# cannonrobot.net
KiCad netlist of a schematic drawn in Altium Designer
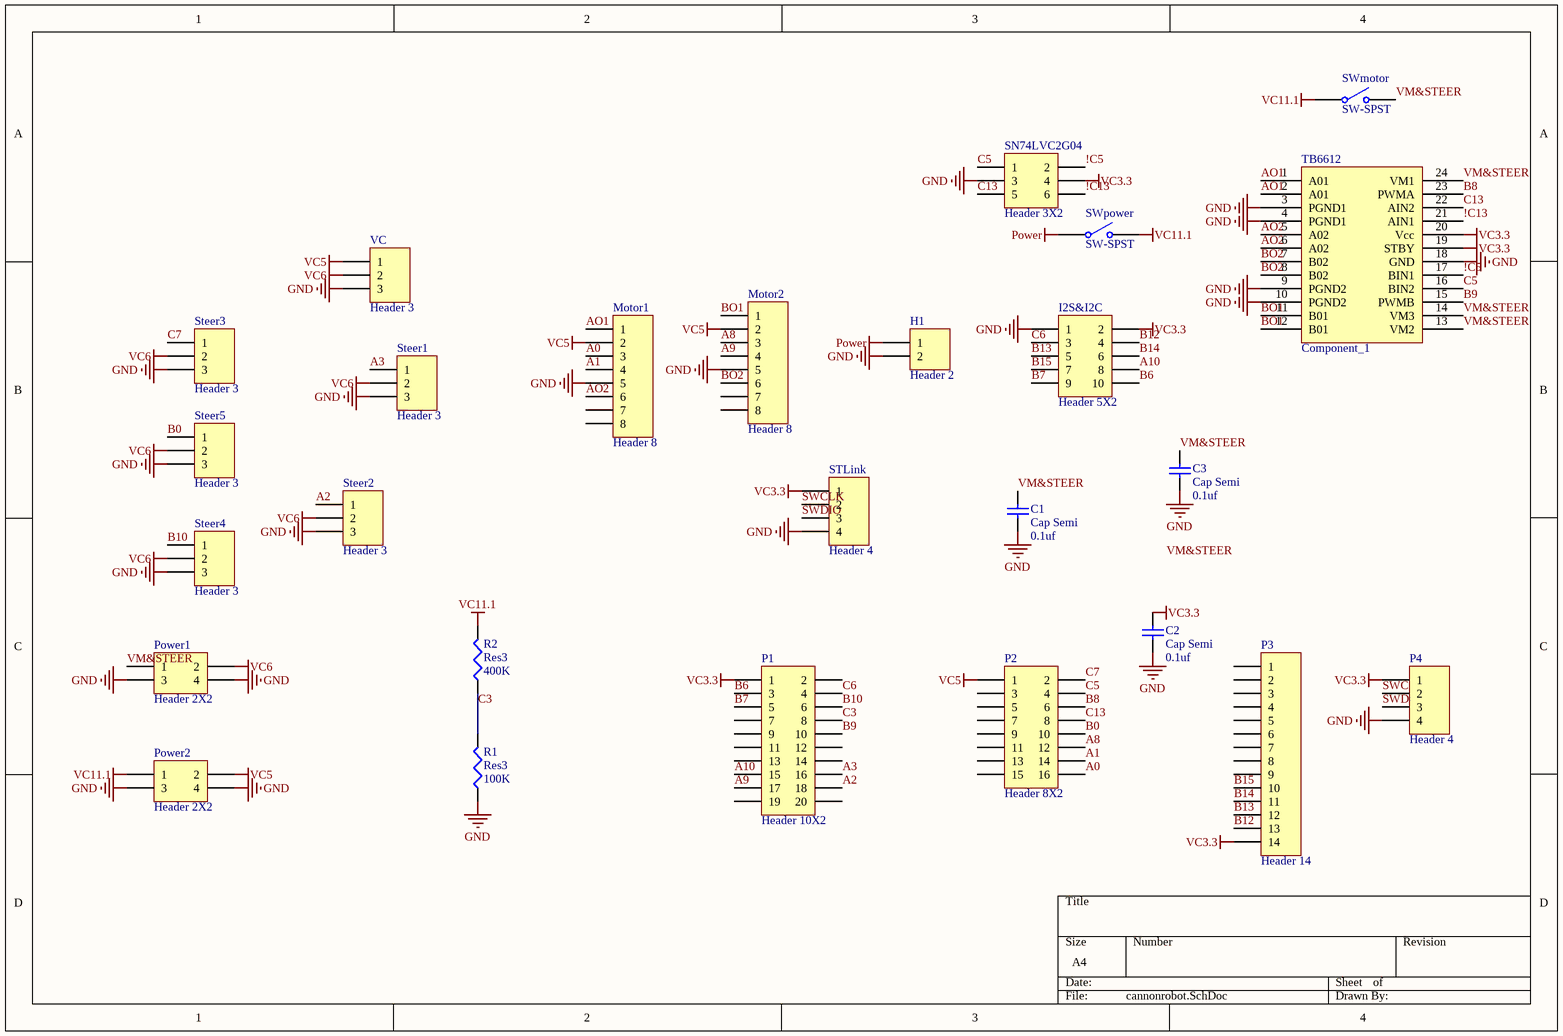
[diagram p0: cannonrobot.SchDoc]

(export (version "E")
  (design (tool "Eeschema 10.0.6"))
  (components
    (comp (ref "C1")
      (value "Cap Semi")
      (footprint "CAPC3225L")
      (description "Capacitor (Semiconductor SIM Model)")
      (fields (field (name "ALTIUM_VALUE") "0.1uf") (field (name "PUBLISHER") "Altium Limited"))
      (libsource (lib "Miscellaneous Devices") (part "Cap Semi"))
    )
    (comp (ref "C2")
      (value "Cap Semi")
      (footprint "CAPC2512L")
      (description "Capacitor (Semiconductor SIM Model)")
      (fields (field (name "ALTIUM_VALUE") "0.1uf") (field (name "PUBLISHER") "Altium Limited"))
      (libsource (lib "Miscellaneous Devices") (part "Cap Semi"))
    )
    (comp (ref "C3")
      (value "Cap Semi")
      (footprint "CAPC2512L")
      (description "Capacitor (Semiconductor SIM Model)")
      (fields (field (name "ALTIUM_VALUE") "0.1uf") (field (name "PUBLISHER") "Altium Limited"))
      (libsource (lib "Miscellaneous Devices") (part "Cap Semi"))
    )
    (comp (ref "H1")
      (value "Header 2")
      (footprint "电源接口:PCBComponent_1")
      (description "Header, 2-Pin")
      (fields (field (name "PUBLISHER") "Altium Limited"))
      (libsource (lib "Miscellaneous Connectors") (part "Header 2"))
    )
    (comp (ref "I2S&I2C")
      (value "Header 5X2")
      (footprint "HDR2X5")
      (description "Header, 5-Pin, Dual row")
      (fields (field (name "PUBLISHER") "Altium Limited"))
      (libsource (lib "Miscellaneous Connectors") (part "Header 5X2"))
    )
    (comp (ref "Motor1")
      (value "Header 8")
      (footprint "J_JAT_A1250WV-S-06P:J_JAT_A1250WV-S-06P")
      (description "Header, 8-Pin")
      (fields (field (name "PUBLISHER") "Altium Limited"))
      (libsource (lib "Miscellaneous Connectors") (part "Header 8"))
    )
    (comp (ref "Motor2")
      (value "Header 8")
      (footprint "J_JAT_A1250WV-S-06P:J_JAT_A1250WV-S-06P")
      (description "Header, 8-Pin")
      (fields (field (name "PUBLISHER") "Altium Limited"))
      (libsource (lib "Miscellaneous Connectors") (part "Header 8"))
    )
    (comp (ref "P1")
      (value "Header 10X2")
      (footprint "HDR2X10")
      (description "Header, 10-Pin, Dual row")
      (fields (field (name "PUBLISHER") "Altium Limited"))
      (libsource (lib "Miscellaneous Connectors") (part "Header 10X2"))
    )
    (comp (ref "P2")
      (value "Header 8X2")
      (footprint "HDR2X8")
      (description "Header, 8-Pin, Dual row")
      (fields (field (name "PUBLISHER") "Altium Limited"))
      (libsource (lib "Miscellaneous Connectors") (part "Header 8X2"))
    )
    (comp (ref "P3")
      (value "Header 14")
      (footprint "HDR1X14")
      (description "Header, 14-Pin")
      (fields (field (name "PUBLISHER") "Altium Limited"))
      (libsource (lib "Miscellaneous Connectors") (part "Header 14"))
    )
    (comp (ref "P4")
      (value "Header 4")
      (footprint "HDR1X4")
      (description "Header, 4-Pin")
      (fields (field (name "PUBLISHER") "Altium Limited"))
      (libsource (lib "Miscellaneous Connectors") (part "Header 4"))
    )
    (comp (ref "Power1")
      (value "Header 2X2")
      (footprint "电源3.3V:PCBComponent_1")
      (description "Header, 2-Pin, Dual row")
      (fields (field (name "PUBLISHER") "Altium Limited"))
      (libsource (lib "Miscellaneous Connectors") (part "Header 2X2"))
    )
    (comp (ref "Power2")
      (value "Header 2X2")
      (footprint "电源3.3V:PCBComponent_1")
      (description "Header, 2-Pin, Dual row")
      (fields (field (name "PUBLISHER") "Altium Limited"))
      (libsource (lib "Miscellaneous Connectors") (part "Header 2X2"))
    )
    (comp (ref "R1")
      (value "Res3")
      (footprint "RESC1608L")
      (description "Resistor")
      (fields (field (name "ALTIUM_VALUE") "100K") (field (name "PUBLISHER") "Altium Limited"))
      (libsource (lib "Miscellaneous Devices") (part "Res3"))
    )
    (comp (ref "R2")
      (value "Res3")
      (footprint "RESC1608L")
      (description "Resistor")
      (fields (field (name "ALTIUM_VALUE") "400K") (field (name "PUBLISHER") "Altium Limited"))
      (libsource (lib "Miscellaneous Devices") (part "Res3"))
    )
    (comp (ref "SN74LVC2G04")
      (value "Header 3X2")
      (footprint "SOT23-6:PCBComponent_1")
      (description "Header, 3-Pin, Dual row")
      (fields (field (name "PUBLISHER") "Altium Limited"))
      (libsource (lib "Miscellaneous Connectors") (part "Header 3X2"))
    )
    (comp (ref "Steer1")
      (value "Header 3")
      (footprint "HDR1X3")
      (description "Header, 3-Pin")
      (fields (field (name "PUBLISHER") "Altium Limited"))
      (libsource (lib "Miscellaneous Connectors") (part "Header 3"))
    )
    (comp (ref "Steer2")
      (value "Header 3")
      (footprint "HDR1X3")
      (description "Header, 3-Pin")
      (fields (field (name "PUBLISHER") "Altium Limited"))
      (libsource (lib "Miscellaneous Connectors") (part "Header 3"))
    )
    (comp (ref "Steer3")
      (value "Header 3")
      (footprint "HDR1X3")
      (description "Header, 3-Pin")
      (fields (field (name "PUBLISHER") "Altium Limited"))
      (libsource (lib "Miscellaneous Connectors") (part "Header 3"))
    )
    (comp (ref "Steer4")
      (value "Header 3")
      (footprint "HDR1X3")
      (description "Header, 3-Pin")
      (fields (field (name "PUBLISHER") "Altium Limited"))
      (libsource (lib "Miscellaneous Connectors") (part "Header 3"))
    )
    (comp (ref "Steer5")
      (value "Header 3")
      (footprint "HDR1X3")
      (description "Header, 3-Pin")
      (fields (field (name "PUBLISHER") "Altium Limited"))
      (libsource (lib "Miscellaneous Connectors") (part "Header 3"))
    )
    (comp (ref "STLink")
      (value "Header 4")
      (footprint "HDR1X4")
      (description "Header, 4-Pin")
      (fields (field (name "PUBLISHER") "Altium Limited"))
      (libsource (lib "Miscellaneous Connectors") (part "Header 4"))
    )
    (comp (ref "SWmotor")
      (value "SW-SPST")
      (footprint "拨动开关:PCBComponent_1")
      (description "Single-Pole, Single-Throw Switch")
      (fields (field (name "PUBLISHER") "Altium Limited"))
      (libsource (lib "Miscellaneous Devices") (part "SW-SPST"))
    )
    (comp (ref "SWpower")
      (value "SW-SPST")
      (footprint "拨动开关:PCBComponent_1")
      (description "Single-Pole, Single-Throw Switch")
      (fields (field (name "PUBLISHER") "Altium Limited"))
      (libsource (lib "Miscellaneous Devices") (part "SW-SPST"))
    )
    (comp (ref "TB6612")
      (value "Component_1")
      (footprint "SSOP24:SSOP24 - duplicate")
      (libsource (lib "TB6612") (part "Component_1"))
    )
    (comp (ref "VC")
      (value "Header 3")
      (footprint "HDR1X3")
      (description "Header, 3-Pin")
      (fields (field (name "PUBLISHER") "Altium Limited"))
      (libsource (lib "Miscellaneous Connectors") (part "Header 3"))
    )
  )
  (nets
    (net (code "1") (name "/!C5") (class "Default")
      (node (ref "SN74LVC2G04") (pin "2") (pinfunction "2_2") (pintype "passive"))
      (node (ref "TB6612") (pin "17") (pinfunction "BIN1_17") (pintype "passive"))
    )
    (net (code "2") (name "/!C13") (class "Default")
      (node (ref "SN74LVC2G04") (pin "6") (pinfunction "6_6") (pintype "passive"))
      (node (ref "TB6612") (pin "21") (pinfunction "AIN1_21") (pintype "passive"))
    )
    (net (code "3") (name "/A0") (class "Default")
      (node (ref "Motor1") (pin "3") (pinfunction "3_3") (pintype "passive"))
      (node (ref "P2") (pin "16") (pinfunction "16_16") (pintype "passive"))
    )
    (net (code "4") (name "/A1") (class "Default")
      (node (ref "Motor1") (pin "4") (pinfunction "4_4") (pintype "passive"))
      (node (ref "P2") (pin "14") (pinfunction "14_14") (pintype "passive"))
    )
    (net (code "5") (name "/A2") (class "Default")
      (node (ref "P1") (pin "18") (pinfunction "18_18") (pintype "passive"))
      (node (ref "Steer2") (pin "1") (pinfunction "1_1") (pintype "passive"))
    )
    (net (code "6") (name "/A3") (class "Default")
      (node (ref "P1") (pin "16") (pinfunction "16_16") (pintype "passive"))
      (node (ref "Steer1") (pin "1") (pinfunction "1_1") (pintype "passive"))
    )
    (net (code "7") (name "/A8") (class "Default")
      (node (ref "Motor2") (pin "3") (pinfunction "3_3") (pintype "passive"))
      (node (ref "P2") (pin "12") (pinfunction "12_12") (pintype "passive"))
    )
    (net (code "8") (name "/A9") (class "Default")
      (node (ref "Motor2") (pin "4") (pinfunction "4_4") (pintype "passive"))
      (node (ref "P1") (pin "17") (pinfunction "17_17") (pintype "passive"))
    )
    (net (code "9") (name "/A10") (class "Default")
      (node (ref "I2S&I2C") (pin "8") (pinfunction "8_8") (pintype "passive"))
      (node (ref "P1") (pin "15") (pinfunction "15_15") (pintype "passive"))
    )
    (net (code "10") (name "/AO1") (class "Default")
      (node (ref "Motor1") (pin "1") (pinfunction "1_1") (pintype "passive"))
      (node (ref "TB6612") (pin "1") (pinfunction "A01_1") (pintype "passive"))
      (node (ref "TB6612") (pin "2") (pinfunction "A01_2") (pintype "passive"))
    )
    (net (code "11") (name "/AO2") (class "Default")
      (node (ref "Motor1") (pin "6") (pinfunction "6_6") (pintype "passive"))
      (node (ref "TB6612") (pin "5") (pinfunction "A02_5") (pintype "passive"))
      (node (ref "TB6612") (pin "6") (pinfunction "A02_6") (pintype "passive"))
    )
    (net (code "12") (name "/B0") (class "Default")
      (node (ref "P2") (pin "10") (pinfunction "10_10") (pintype "passive"))
      (node (ref "Steer5") (pin "1") (pinfunction "1_1") (pintype "passive"))
    )
    (net (code "13") (name "/B6") (class "Default")
      (node (ref "I2S&I2C") (pin "10") (pinfunction "10_10") (pintype "passive"))
      (node (ref "P1") (pin "3") (pinfunction "3_3") (pintype "passive"))
    )
    (net (code "14") (name "/B7") (class "Default")
      (node (ref "I2S&I2C") (pin "9") (pinfunction "9_9") (pintype "passive"))
      (node (ref "P1") (pin "5") (pinfunction "5_5") (pintype "passive"))
    )
    (net (code "15") (name "/B8") (class "Default")
      (node (ref "P2") (pin "6") (pinfunction "6_6") (pintype "passive"))
      (node (ref "TB6612") (pin "23") (pinfunction "PWMA_23") (pintype "passive"))
    )
    (net (code "16") (name "/B9") (class "Default")
      (node (ref "P1") (pin "10") (pinfunction "10_10") (pintype "passive"))
      (node (ref "TB6612") (pin "15") (pinfunction "PWMB_15") (pintype "passive"))
    )
    (net (code "17") (name "/B10") (class "Default")
      (node (ref "P1") (pin "6") (pinfunction "6_6") (pintype "passive"))
      (node (ref "Steer4") (pin "1") (pinfunction "1_1") (pintype "passive"))
    )
    (net (code "18") (name "/B12") (class "Default")
      (node (ref "I2S&I2C") (pin "4") (pinfunction "4_4") (pintype "passive"))
      (node (ref "P3") (pin "13") (pinfunction "13_13") (pintype "passive"))
    )
    (net (code "19") (name "/B13") (class "Default")
      (node (ref "I2S&I2C") (pin "5") (pinfunction "5_5") (pintype "passive"))
      (node (ref "P3") (pin "12") (pinfunction "12_12") (pintype "passive"))
    )
    (net (code "20") (name "/B14") (class "Default")
      (node (ref "I2S&I2C") (pin "6") (pinfunction "6_6") (pintype "passive"))
      (node (ref "P3") (pin "11") (pinfunction "11_11") (pintype "passive"))
    )
    (net (code "21") (name "/B15") (class "Default")
      (node (ref "I2S&I2C") (pin "7") (pinfunction "7_7") (pintype "passive"))
      (node (ref "P3") (pin "10") (pinfunction "10_10") (pintype "passive"))
    )
    (net (code "22") (name "/BO1") (class "Default")
      (node (ref "Motor2") (pin "1") (pinfunction "1_1") (pintype "passive"))
      (node (ref "TB6612") (pin "11") (pinfunction "B01_11") (pintype "passive"))
      (node (ref "TB6612") (pin "12") (pinfunction "B01_12") (pintype "passive"))
    )
    (net (code "23") (name "/BO2") (class "Default")
      (node (ref "Motor2") (pin "6") (pinfunction "6_6") (pintype "passive"))
      (node (ref "TB6612") (pin "7") (pinfunction "B02_7") (pintype "passive"))
      (node (ref "TB6612") (pin "8") (pinfunction "B02_8") (pintype "passive"))
    )
    (net (code "24") (name "/C3") (class "Default")
      (node (ref "P1") (pin "8") (pinfunction "8_8") (pintype "passive"))
      (node (ref "R1") (pin "2") (pinfunction "2_2") (pintype "passive"))
      (node (ref "R2") (pin "1") (pinfunction "1_1") (pintype "passive"))
    )
    (net (code "25") (name "/C5") (class "Default")
      (node (ref "P2") (pin "4") (pinfunction "4_4") (pintype "passive"))
      (node (ref "SN74LVC2G04") (pin "1") (pinfunction "1_1") (pintype "passive"))
      (node (ref "TB6612") (pin "16") (pinfunction "BIN2_16") (pintype "passive"))
    )
    (net (code "26") (name "/C6") (class "Default")
      (node (ref "I2S&I2C") (pin "3") (pinfunction "3_3") (pintype "passive"))
      (node (ref "P1") (pin "4") (pinfunction "4_4") (pintype "passive"))
    )
    (net (code "27") (name "/C7") (class "Default")
      (node (ref "P2") (pin "2") (pinfunction "2_2") (pintype "passive"))
      (node (ref "Steer3") (pin "1") (pinfunction "1_1") (pintype "passive"))
    )
    (net (code "28") (name "/C13") (class "Default")
      (node (ref "P2") (pin "8") (pinfunction "8_8") (pintype "passive"))
      (node (ref "SN74LVC2G04") (pin "5") (pinfunction "5_5") (pintype "passive"))
      (node (ref "TB6612") (pin "22") (pinfunction "AIN2_22") (pintype "passive"))
    )
    (net (code "29") (name "/SWCLK") (class "Default")
      (node (ref "P4") (pin "2") (pinfunction "2_2") (pintype "passive"))
      (node (ref "STLink") (pin "2") (pinfunction "2_2") (pintype "passive"))
    )
    (net (code "30") (name "/SWDIO") (class "Default")
      (node (ref "P4") (pin "3") (pinfunction "3_3") (pintype "passive"))
      (node (ref "STLink") (pin "3") (pinfunction "3_3") (pintype "passive"))
    )
    (net (code "31") (name "/VM&STEER") (class "Default")
      (node (ref "C1") (pin "2") (pinfunction "2_2") (pintype "passive"))
      (node (ref "C3") (pin "2") (pinfunction "2_2") (pintype "passive"))
      (node (ref "Power1") (pin "1") (pinfunction "1_1") (pintype "passive"))
      (node (ref "SWmotor") (pin "2") (pinfunction "NO_2") (pintype "passive"))
      (node (ref "TB6612") (pin "13") (pinfunction "VM2_13") (pintype "passive"))
      (node (ref "TB6612") (pin "14") (pinfunction "VM3_14") (pintype "passive"))
      (node (ref "TB6612") (pin "24") (pinfunction "VM1_24") (pintype "passive"))
    )
    (net (code "32") (name "GND") (class "Default")
      (node (ref "C1") (pin "1") (pinfunction "1_1") (pintype "passive"))
      (node (ref "C2") (pin "1") (pinfunction "1_1") (pintype "passive"))
      (node (ref "C3") (pin "1") (pinfunction "1_1") (pintype "passive"))
      (node (ref "H1") (pin "2") (pinfunction "2_2") (pintype "passive"))
      (node (ref "I2S&I2C") (pin "1") (pinfunction "1_1") (pintype "passive"))
      (node (ref "Motor1") (pin "5") (pinfunction "5_5") (pintype "passive"))
      (node (ref "Motor2") (pin "5") (pinfunction "5_5") (pintype "passive"))
      (node (ref "P4") (pin "4") (pinfunction "4_4") (pintype "passive"))
      (node (ref "Power1") (pin "3") (pinfunction "3_3") (pintype "passive"))
      (node (ref "Power1") (pin "4") (pinfunction "4_4") (pintype "passive"))
      (node (ref "Power2") (pin "3") (pinfunction "3_3") (pintype "passive"))
      (node (ref "Power2") (pin "4") (pinfunction "4_4") (pintype "passive"))
      (node (ref "R1") (pin "1") (pinfunction "1_1") (pintype "passive"))
      (node (ref "SN74LVC2G04") (pin "3") (pinfunction "3_3") (pintype "passive"))
      (node (ref "STLink") (pin "4") (pinfunction "4_4") (pintype "passive"))
      (node (ref "Steer1") (pin "3") (pinfunction "3_3") (pintype "passive"))
      (node (ref "Steer2") (pin "3") (pinfunction "3_3") (pintype "passive"))
      (node (ref "Steer3") (pin "3") (pinfunction "3_3") (pintype "passive"))
      (node (ref "Steer4") (pin "3") (pinfunction "3_3") (pintype "passive"))
      (node (ref "Steer5") (pin "3") (pinfunction "3_3") (pintype "passive"))
      (node (ref "TB6612") (pin "10") (pinfunction "PGND2_10") (pintype "passive"))
      (node (ref "TB6612") (pin "18") (pinfunction "GND_18") (pintype "passive"))
      (node (ref "TB6612") (pin "3") (pinfunction "PGND1_3") (pintype "passive"))
      (node (ref "TB6612") (pin "4") (pinfunction "PGND1_4") (pintype "passive"))
      (node (ref "TB6612") (pin "9") (pinfunction "PGND2_9") (pintype "passive"))
      (node (ref "VC") (pin "3") (pinfunction "3_3") (pintype "passive"))
    )
    (net (code "33") (name "Power") (class "Default")
      (node (ref "H1") (pin "1") (pinfunction "1_1") (pintype "passive"))
      (node (ref "SWpower") (pin "1") (pinfunction "COMMON_1") (pintype "passive"))
    )
    (net (code "34") (name "VC3.3") (class "Default")
      (node (ref "C2") (pin "2") (pinfunction "2_2") (pintype "passive"))
      (node (ref "I2S&I2C") (pin "2") (pinfunction "2_2") (pintype "passive"))
      (node (ref "P1") (pin "1") (pinfunction "1_1") (pintype "passive"))
      (node (ref "P3") (pin "14") (pinfunction "14_14") (pintype "passive"))
      (node (ref "P4") (pin "1") (pinfunction "1_1") (pintype "passive"))
      (node (ref "SN74LVC2G04") (pin "4") (pinfunction "4_4") (pintype "passive"))
      (node (ref "STLink") (pin "1") (pinfunction "1_1") (pintype "passive"))
      (node (ref "TB6612") (pin "19") (pinfunction "STBY_19") (pintype "passive"))
      (node (ref "TB6612") (pin "20") (pinfunction "Vcc_20") (pintype "passive"))
    )
    (net (code "35") (name "VC5") (class "Default")
      (node (ref "Motor1") (pin "2") (pinfunction "2_2") (pintype "passive"))
      (node (ref "Motor2") (pin "2") (pinfunction "2_2") (pintype "passive"))
      (node (ref "P2") (pin "1") (pinfunction "1_1") (pintype "passive"))
      (node (ref "Power2") (pin "2") (pinfunction "2_2") (pintype "passive"))
      (node (ref "VC") (pin "1") (pinfunction "1_1") (pintype "passive"))
    )
    (net (code "36") (name "VC6") (class "Default")
      (node (ref "Power1") (pin "2") (pinfunction "2_2") (pintype "passive"))
      (node (ref "Steer1") (pin "2") (pinfunction "2_2") (pintype "passive"))
      (node (ref "Steer2") (pin "2") (pinfunction "2_2") (pintype "passive"))
      (node (ref "Steer3") (pin "2") (pinfunction "2_2") (pintype "passive"))
      (node (ref "Steer4") (pin "2") (pinfunction "2_2") (pintype "passive"))
      (node (ref "Steer5") (pin "2") (pinfunction "2_2") (pintype "passive"))
      (node (ref "VC") (pin "2") (pinfunction "2_2") (pintype "passive"))
    )
    (net (code "37") (name "VC11.1") (class "Default")
      (node (ref "Power2") (pin "1") (pinfunction "1_1") (pintype "passive"))
      (node (ref "R2") (pin "2") (pinfunction "2_2") (pintype "passive"))
      (node (ref "SWmotor") (pin "1") (pinfunction "COMMON_1") (pintype "passive"))
      (node (ref "SWpower") (pin "2") (pinfunction "NO_2") (pintype "passive"))
    )
    (net (code "38") (name "unconnected-(Motor1-Pad7)") (class "Default")
      (node (ref "Motor1") (pin "7") (pinfunction "7_7") (pintype "passive"))
    )
    (net (code "39") (name "unconnected-(Motor1-Pad8)") (class "Default")
      (node (ref "Motor1") (pin "8") (pinfunction "8_8") (pintype "passive"))
    )
    (net (code "40") (name "unconnected-(Motor2-Pad7)") (class "Default")
      (node (ref "Motor2") (pin "7") (pinfunction "7_7") (pintype "passive"))
    )
    (net (code "41") (name "unconnected-(Motor2-Pad8)") (class "Default")
      (node (ref "Motor2") (pin "8") (pinfunction "8_8") (pintype "passive"))
    )
    (net (code "42") (name "unconnected-(P1-Pad2)") (class "Default")
      (node (ref "P1") (pin "2") (pinfunction "2_2") (pintype "passive"))
    )
    (net (code "43") (name "unconnected-(P1-Pad7)") (class "Default")
      (node (ref "P1") (pin "7") (pinfunction "7_7") (pintype "passive"))
    )
    (net (code "44") (name "unconnected-(P1-Pad9)") (class "Default")
      (node (ref "P1") (pin "9") (pinfunction "9_9") (pintype "passive"))
    )
    (net (code "45") (name "unconnected-(P1-Pad11)") (class "Default")
      (node (ref "P1") (pin "11") (pinfunction "11_11") (pintype "passive"))
    )
    (net (code "46") (name "unconnected-(P1-Pad12)") (class "Default")
      (node (ref "P1") (pin "12") (pinfunction "12_12") (pintype "passive"))
    )
    (net (code "47") (name "unconnected-(P1-Pad13)") (class "Default")
      (node (ref "P1") (pin "13") (pinfunction "13_13") (pintype "passive"))
    )
    (net (code "48") (name "unconnected-(P1-Pad14)") (class "Default")
      (node (ref "P1") (pin "14") (pinfunction "14_14") (pintype "passive"))
    )
    (net (code "49") (name "unconnected-(P1-Pad19)") (class "Default")
      (node (ref "P1") (pin "19") (pinfunction "19_19") (pintype "passive"))
    )
    (net (code "50") (name "unconnected-(P1-Pad20)") (class "Default")
      (node (ref "P1") (pin "20") (pinfunction "20_20") (pintype "passive"))
    )
    (net (code "51") (name "unconnected-(P2-Pad3)") (class "Default")
      (node (ref "P2") (pin "3") (pinfunction "3_3") (pintype "passive"))
    )
    (net (code "52") (name "unconnected-(P2-Pad5)") (class "Default")
      (node (ref "P2") (pin "5") (pinfunction "5_5") (pintype "passive"))
    )
    (net (code "53") (name "unconnected-(P2-Pad7)") (class "Default")
      (node (ref "P2") (pin "7") (pinfunction "7_7") (pintype "passive"))
    )
    (net (code "54") (name "unconnected-(P2-Pad9)") (class "Default")
      (node (ref "P2") (pin "9") (pinfunction "9_9") (pintype "passive"))
    )
    (net (code "55") (name "unconnected-(P2-Pad11)") (class "Default")
      (node (ref "P2") (pin "11") (pinfunction "11_11") (pintype "passive"))
    )
    (net (code "56") (name "unconnected-(P2-Pad13)") (class "Default")
      (node (ref "P2") (pin "13") (pinfunction "13_13") (pintype "passive"))
    )
    (net (code "57") (name "unconnected-(P2-Pad15)") (class "Default")
      (node (ref "P2") (pin "15") (pinfunction "15_15") (pintype "passive"))
    )
    (net (code "58") (name "unconnected-(P3-Pad1)") (class "Default")
      (node (ref "P3") (pin "1") (pinfunction "1_1") (pintype "passive"))
    )
    (net (code "59") (name "unconnected-(P3-Pad2)") (class "Default")
      (node (ref "P3") (pin "2") (pinfunction "2_2") (pintype "passive"))
    )
    (net (code "60") (name "unconnected-(P3-Pad3)") (class "Default")
      (node (ref "P3") (pin "3") (pinfunction "3_3") (pintype "passive"))
    )
    (net (code "61") (name "unconnected-(P3-Pad4)") (class "Default")
      (node (ref "P3") (pin "4") (pinfunction "4_4") (pintype "passive"))
    )
    (net (code "62") (name "unconnected-(P3-Pad5)") (class "Default")
      (node (ref "P3") (pin "5") (pinfunction "5_5") (pintype "passive"))
    )
    (net (code "63") (name "unconnected-(P3-Pad6)") (class "Default")
      (node (ref "P3") (pin "6") (pinfunction "6_6") (pintype "passive"))
    )
    (net (code "64") (name "unconnected-(P3-Pad7)") (class "Default")
      (node (ref "P3") (pin "7") (pinfunction "7_7") (pintype "passive"))
    )
    (net (code "65") (name "unconnected-(P3-Pad8)") (class "Default")
      (node (ref "P3") (pin "8") (pinfunction "8_8") (pintype "passive"))
    )
    (net (code "66") (name "unconnected-(P3-Pad9)") (class "Default")
      (node (ref "P3") (pin "9") (pinfunction "9_9") (pintype "passive"))
    )
  )
)
